# esp8266-dev-board.net
KiCad netlist of a schematic drawn in EAGLE
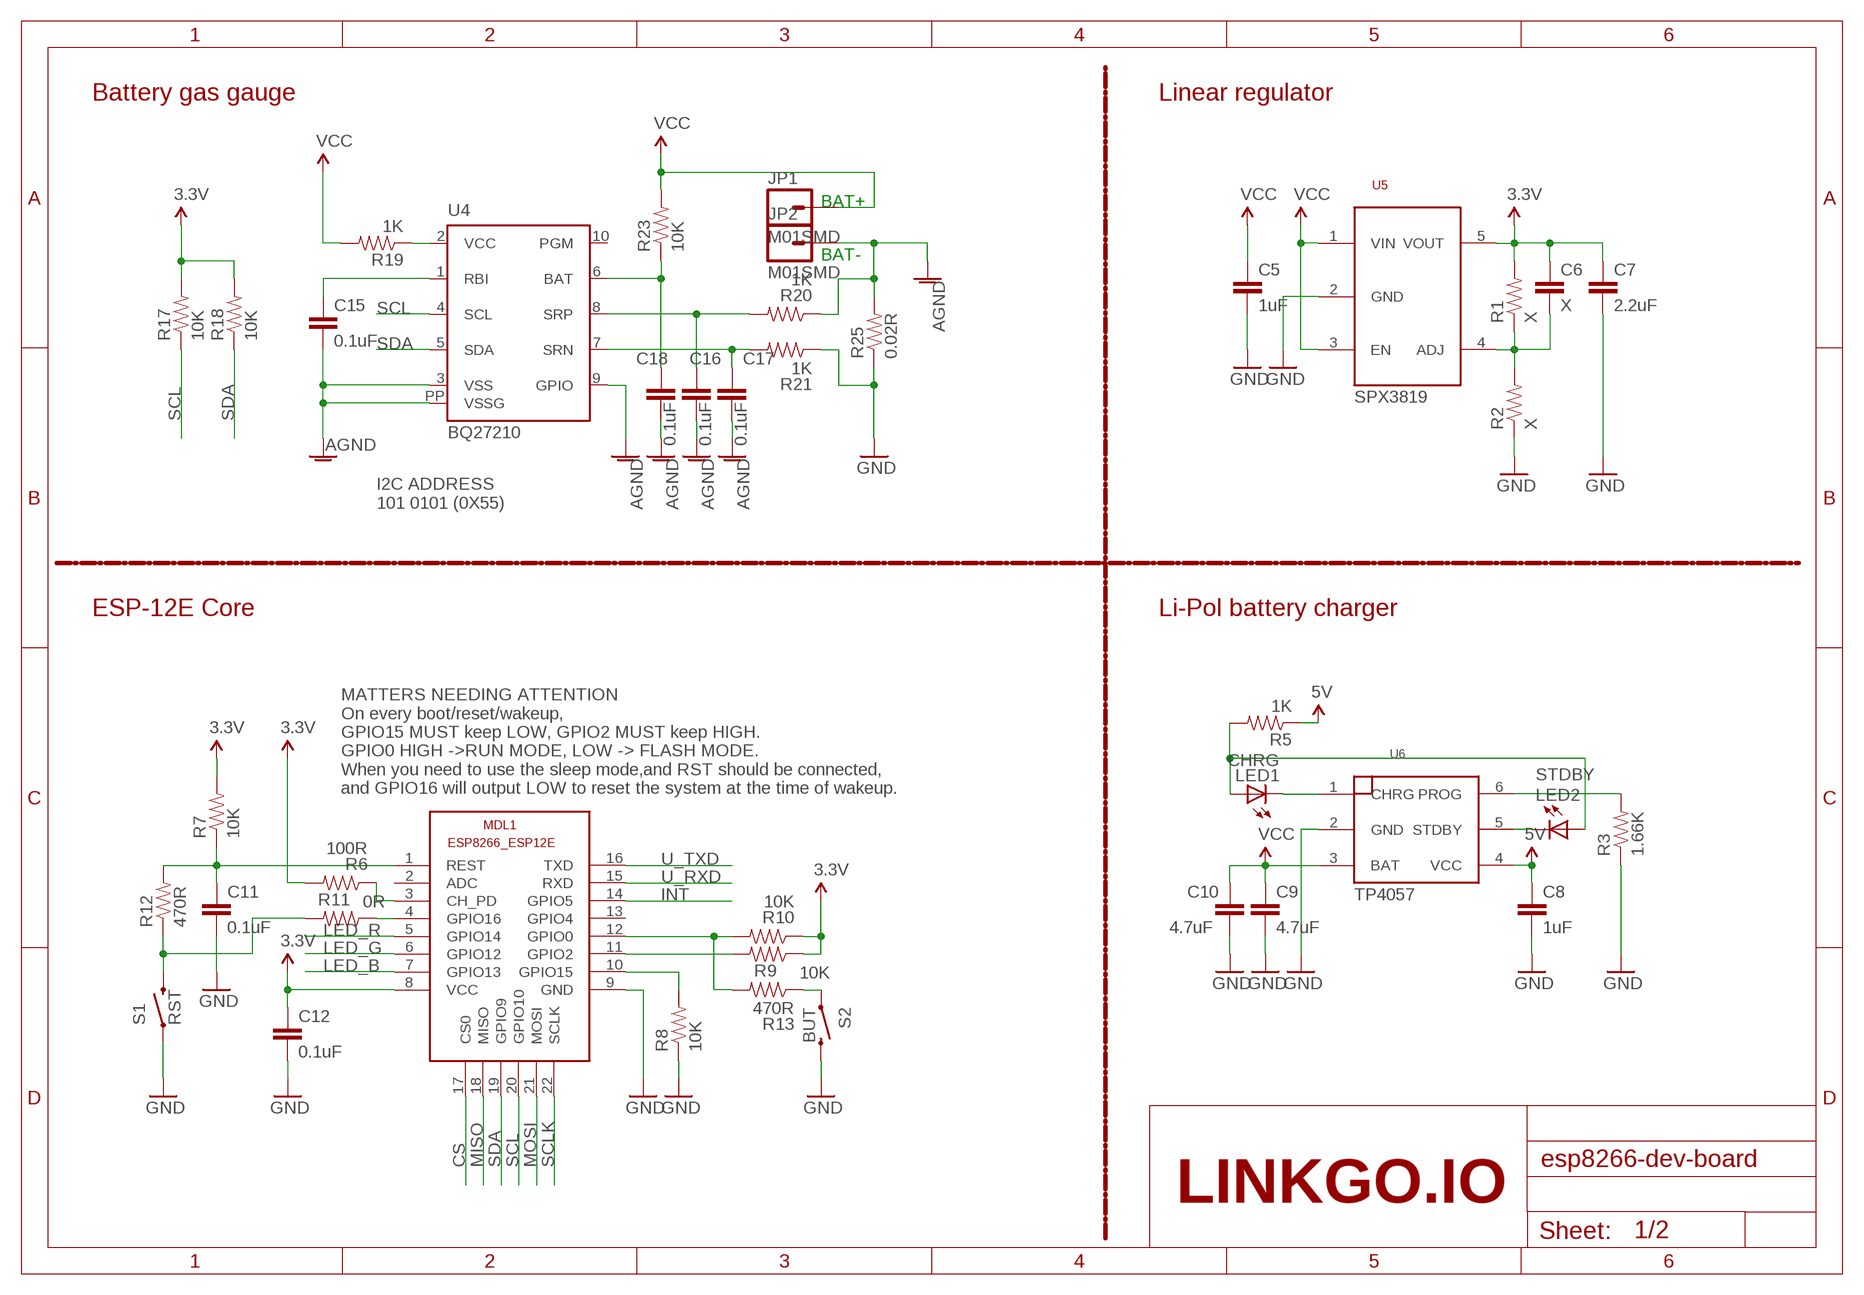
[diagram p0: schematic, sheet 1]
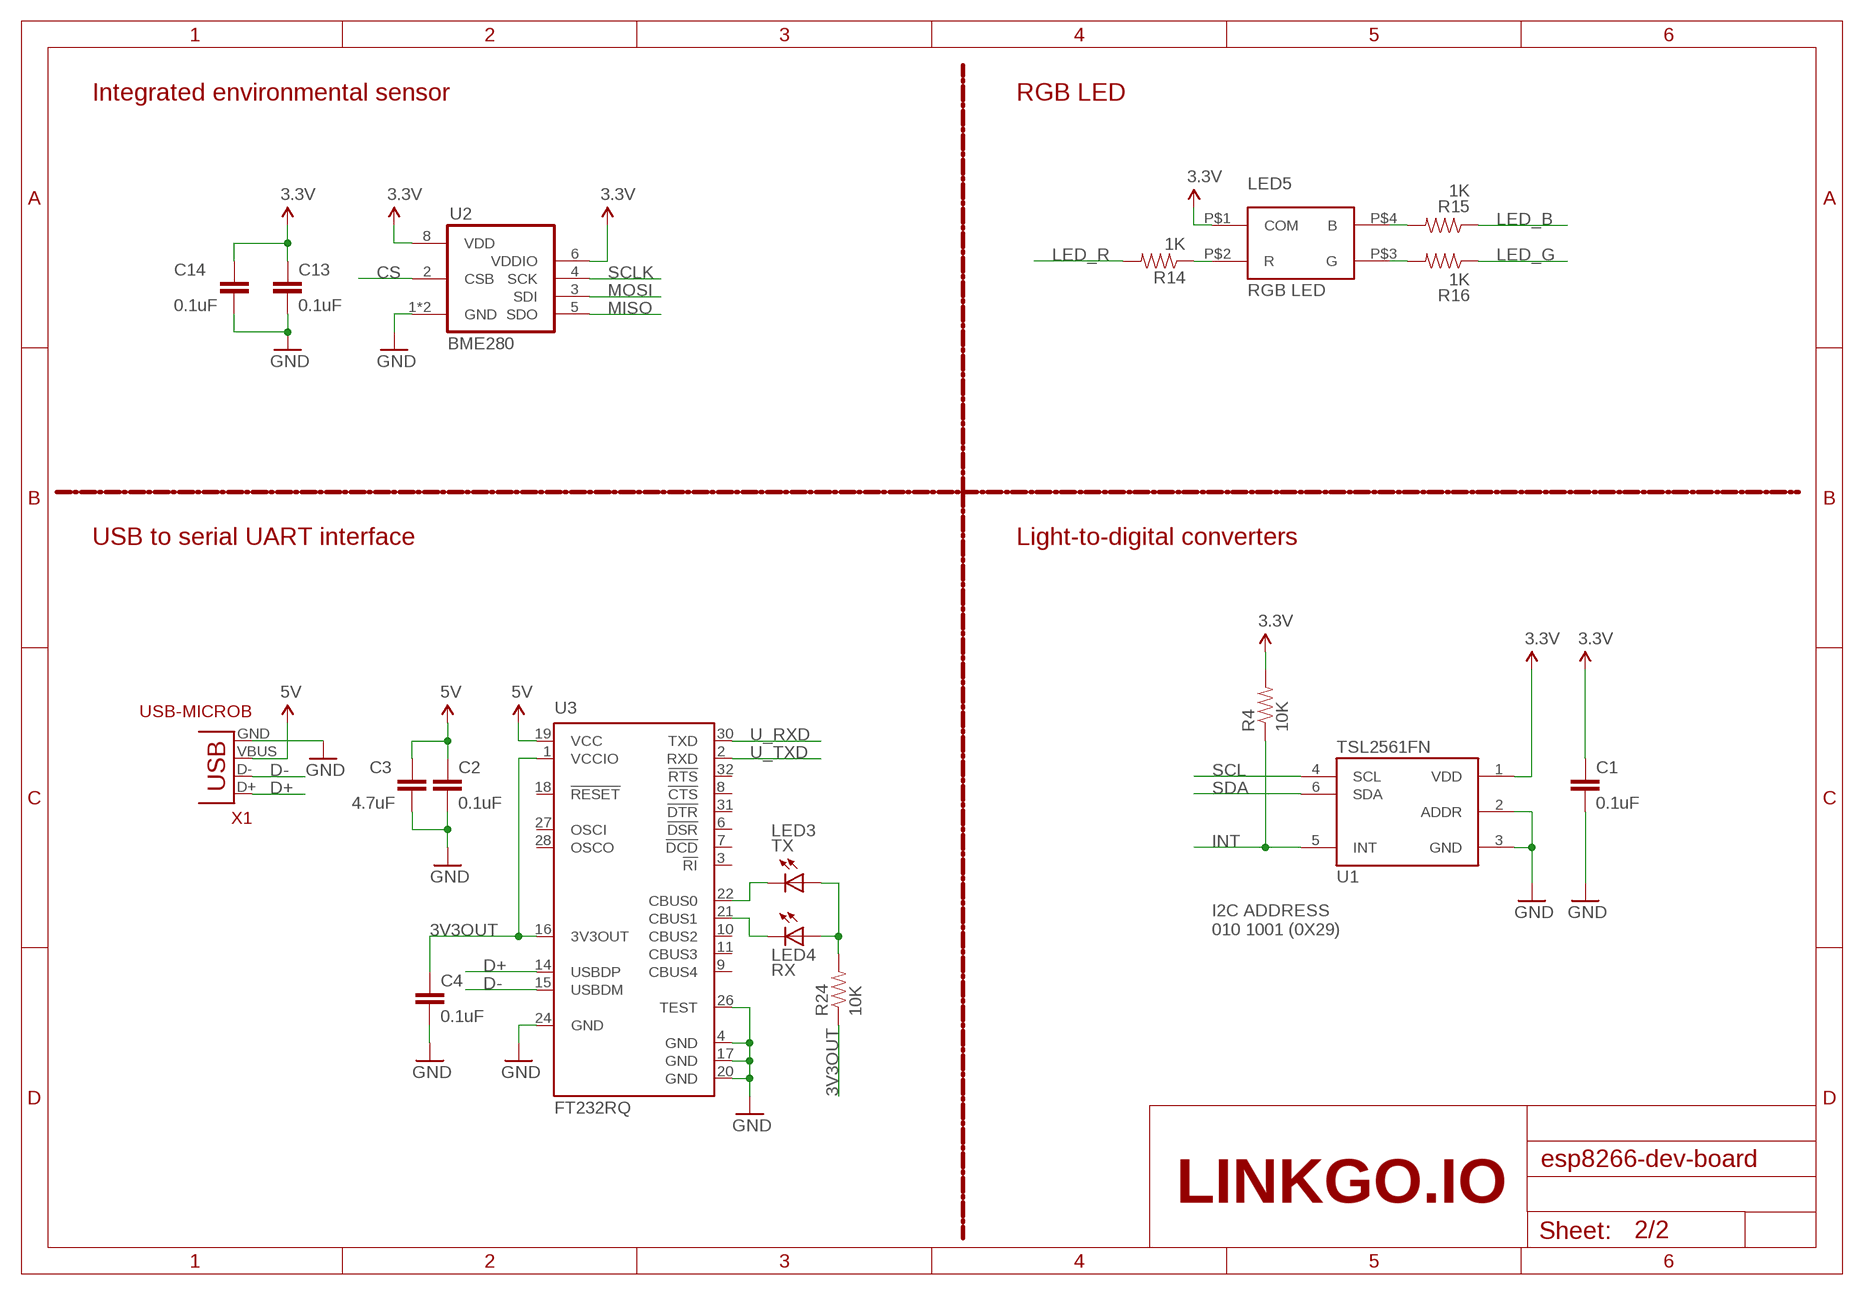
[diagram p1: schematic, sheet 2]

(export (version "E")
  (design (tool "Eeschema 10.0.6"))
  (components
    (comp (ref "C1")
      (value "0.1uF")
      (footprint "eagle-import:0603-CAP")
      (libsource (lib "eagle-import") (part "0.1UF-25V(+80/-20%)(0603)"))
    )
    (comp (ref "C2")
      (value "0.1uF")
      (footprint "eagle-import:0603-CAP")
      (libsource (lib "eagle-import") (part "0.1UF-25V(+80/-20%)(0603)"))
    )
    (comp (ref "C3")
      (value "4.7uF")
      (footprint "eagle-import:0603-CAP")
      (libsource (lib "eagle-import") (part "0.1UF-25V(+80/-20%)(0603)"))
    )
    (comp (ref "C4")
      (value "0.1uF")
      (footprint "eagle-import:0603-CAP")
      (libsource (lib "eagle-import") (part "0.1UF-25V(+80/-20%)(0603)"))
    )
    (comp (ref "C13")
      (value "0.1uF")
      (footprint "eagle-import:0603-CAP")
      (libsource (lib "eagle-import") (part "0.1UF-25V(+80/-20%)(0603)"))
    )
    (comp (ref "C14")
      (value "0.1uF")
      (footprint "eagle-import:0603-CAP")
      (libsource (lib "eagle-import") (part "0.1UF-25V(+80/-20%)(0603)"))
    )
    (comp (ref "LED3")
      (value "TX")
      (footprint "eagle-import:LED-0603")
      (libsource (lib "eagle-import") (part "LED0603"))
    )
    (comp (ref "LED4")
      (value "RX")
      (footprint "eagle-import:LED-0603")
      (libsource (lib "eagle-import") (part "LED0603"))
    )
    (comp (ref "LED5")
      (value "0603RGB")
      (footprint "eagle-import:0603RGB")
      (libsource (lib "eagle-import") (part "0603RGB"))
    )
    (comp (ref "R4")
      (value "10K")
      (footprint "eagle-import:0603-RES")
      (libsource (lib "eagle-import") (part "10KOHM-1/10W-1%(0603)0603"))
    )
    (comp (ref "R14")
      (value "1K")
      (footprint "eagle-import:0603-RES")
      (libsource (lib "eagle-import") (part "10KOHM-1/10W-1%(0603)0603"))
    )
    (comp (ref "R15")
      (value "1K")
      (footprint "eagle-import:0603-RES")
      (libsource (lib "eagle-import") (part "10KOHM-1/10W-1%(0603)0603"))
    )
    (comp (ref "R16")
      (value "1K")
      (footprint "eagle-import:0603-RES")
      (libsource (lib "eagle-import") (part "10KOHM-1/10W-1%(0603)0603"))
    )
    (comp (ref "R24")
      (value "10K")
      (footprint "eagle-import:0603-RES")
      (libsource (lib "eagle-import") (part "10KOHM-1/10W-1%(0603)0603"))
    )
    (comp (ref "U1")
      (value "TSL2561FN")
      (footprint "eagle-import:FN-6")
      (libsource (lib "eagle-import") (part "TSL2561FN"))
    )
    (comp (ref "U2")
      (value "BME280")
      (footprint "eagle-import:BME280")
      (libsource (lib "eagle-import") (part "BME280"))
    )
    (comp (ref "U3")
      (value "FT232RQ")
      (footprint "eagle-import:QFN32")
      (libsource (lib "eagle-import") (part "FT232RQ"))
    )
    (comp (ref "X1")
      (value "USB-MICROB")
      (footprint "eagle-import:USB-MICROB")
      (libsource (lib "eagle-import") (part "USB-MICROB"))
    )
    (comp (ref "C5")
      (value "1uF")
      (footprint "eagle-import:0603-CAP")
      (libsource (lib "eagle-import") (part "0.1UF-25V(+80/-20%)(0603)"))
    )
    (comp (ref "C6")
      (value "X")
      (footprint "eagle-import:0603-CAP")
      (libsource (lib "eagle-import") (part "0.1UF-25V(+80/-20%)(0603)"))
    )
    (comp (ref "C7")
      (value "2.2uF")
      (footprint "eagle-import:0603-CAP")
      (libsource (lib "eagle-import") (part "0.1UF-25V(+80/-20%)(0603)"))
    )
    (comp (ref "C8")
      (value "1uF")
      (footprint "eagle-import:0603-CAP")
      (libsource (lib "eagle-import") (part "0.1UF-25V(+80/-20%)(0603)"))
    )
    (comp (ref "C9")
      (value "4.7uF")
      (footprint "eagle-import:0603-CAP")
      (libsource (lib "eagle-import") (part "0.1UF-25V(+80/-20%)(0603)"))
    )
    (comp (ref "C10")
      (value "4.7uF")
      (footprint "eagle-import:0603-CAP")
      (libsource (lib "eagle-import") (part "0.1UF-25V(+80/-20%)(0603)"))
    )
    (comp (ref "C11")
      (value "0.1uF")
      (footprint "eagle-import:0603-CAP")
      (libsource (lib "eagle-import") (part "0.1UF-25V(+80/-20%)(0603)"))
    )
    (comp (ref "C12")
      (value "0.1uF")
      (footprint "eagle-import:0603-CAP")
      (libsource (lib "eagle-import") (part "0.1UF-25V(+80/-20%)(0603)"))
    )
    (comp (ref "C15")
      (value "0.1uF")
      (footprint "eagle-import:0603-CAP")
      (libsource (lib "eagle-import") (part "0.1UF-25V(+80/-20%)(0603)"))
    )
    (comp (ref "C16")
      (value "0.1uF")
      (footprint "eagle-import:0603-CAP")
      (libsource (lib "eagle-import") (part "0.1UF-25V(+80/-20%)(0603)"))
    )
    (comp (ref "C17")
      (value "0.1uF")
      (footprint "eagle-import:0603-CAP")
      (libsource (lib "eagle-import") (part "0.1UF-25V(+80/-20%)(0603)"))
    )
    (comp (ref "C18")
      (value "0.1uF")
      (footprint "eagle-import:0603-CAP")
      (libsource (lib "eagle-import") (part "0.1UF-25V(+80/-20%)(0603)"))
    )
    (comp (ref "JP1")
      (value "M01SMD")
      (footprint "eagle-import:LUXEON-PAD")
      (libsource (lib "eagle-import") (part "M01SMD"))
    )
    (comp (ref "JP2")
      (value "M01SMD")
      (footprint "eagle-import:LUXEON-PAD")
      (libsource (lib "eagle-import") (part "M01SMD"))
    )
    (comp (ref "LED1")
      (value "CHRG")
      (footprint "eagle-import:LED-0603")
      (libsource (lib "eagle-import") (part "LED0603"))
    )
    (comp (ref "LED2")
      (value "STDBY")
      (footprint "eagle-import:LED-0603")
      (libsource (lib "eagle-import") (part "LED0603"))
    )
    (comp (ref "MDL1")
      (value "ESP8266-12EESP8266-ESP12E")
      (footprint "eagle-import:ESP8266-ESP12E")
      (libsource (lib "eagle-import") (part "ESP8266-12EESP8266-ESP12E"))
    )
    (comp (ref "R1")
      (value "X")
      (footprint "eagle-import:0603-RES")
      (libsource (lib "eagle-import") (part "10KOHM-1/10W-1%(0603)0603"))
    )
    (comp (ref "R2")
      (value "X")
      (footprint "eagle-import:0603-RES")
      (libsource (lib "eagle-import") (part "10KOHM-1/10W-1%(0603)0603"))
    )
    (comp (ref "R3")
      (value "1.66K")
      (footprint "eagle-import:0603-RES")
      (libsource (lib "eagle-import") (part "10KOHM-1/10W-1%(0603)0603"))
    )
    (comp (ref "R5")
      (value "1K")
      (footprint "eagle-import:0603-RES")
      (libsource (lib "eagle-import") (part "10KOHM-1/10W-1%(0603)0603"))
    )
    (comp (ref "R6")
      (value "100R")
      (footprint "eagle-import:0603-RES")
      (libsource (lib "eagle-import") (part "10KOHM-1/10W-1%(0603)0603"))
    )
    (comp (ref "R7")
      (value "10K")
      (footprint "eagle-import:0603-RES")
      (libsource (lib "eagle-import") (part "10KOHM-1/10W-1%(0603)0603"))
    )
    (comp (ref "R8")
      (value "10K")
      (footprint "eagle-import:0603-RES")
      (libsource (lib "eagle-import") (part "10KOHM-1/10W-1%(0603)0603"))
    )
    (comp (ref "R9")
      (value "10K")
      (footprint "eagle-import:0603-RES")
      (libsource (lib "eagle-import") (part "10KOHM-1/10W-1%(0603)0603"))
    )
    (comp (ref "R10")
      (value "10K")
      (footprint "eagle-import:0603-RES")
      (libsource (lib "eagle-import") (part "10KOHM-1/10W-1%(0603)0603"))
    )
    (comp (ref "R11")
      (value "0R")
      (footprint "eagle-import:0603-RES")
      (libsource (lib "eagle-import") (part "10KOHM-1/10W-1%(0603)0603"))
    )
    (comp (ref "R12")
      (value "470R")
      (footprint "eagle-import:0603-RES")
      (libsource (lib "eagle-import") (part "10KOHM-1/10W-1%(0603)0603"))
    )
    (comp (ref "R13")
      (value "470R")
      (footprint "eagle-import:0603-RES")
      (libsource (lib "eagle-import") (part "10KOHM-1/10W-1%(0603)0603"))
    )
    (comp (ref "R17")
      (value "10K")
      (footprint "eagle-import:0603-RES")
      (libsource (lib "eagle-import") (part "10KOHM-1/10W-1%(0603)0603"))
    )
    (comp (ref "R18")
      (value "10K")
      (footprint "eagle-import:0603-RES")
      (libsource (lib "eagle-import") (part "10KOHM-1/10W-1%(0603)0603"))
    )
    (comp (ref "R19")
      (value "1K")
      (footprint "eagle-import:0603-RES")
      (libsource (lib "eagle-import") (part "10KOHM-1/10W-1%(0603)0603"))
    )
    (comp (ref "R20")
      (value "1K")
      (footprint "eagle-import:0603-RES")
      (libsource (lib "eagle-import") (part "10KOHM-1/10W-1%(0603)0603"))
    )
    (comp (ref "R21")
      (value "1K")
      (footprint "eagle-import:0603-RES")
      (libsource (lib "eagle-import") (part "10KOHM-1/10W-1%(0603)0603"))
    )
    (comp (ref "R23")
      (value "10K")
      (footprint "eagle-import:0603-RES")
      (libsource (lib "eagle-import") (part "10KOHM-1/10W-1%(0603)0603"))
    )
    (comp (ref "R25")
      (value "0.02R")
      (footprint "eagle-import:1206")
      (libsource (lib "eagle-import") (part "RESISTOR1206"))
    )
    (comp (ref "S1")
      (value "RST")
      (footprint "eagle-import:TACTILE-SWITCH-1101NE")
      (libsource (lib "eagle-import") (part "SWITCH-MOMENTARY-2-SMD-1101NE"))
    )
    (comp (ref "S2")
      (value "BUT")
      (footprint "eagle-import:TACTILE-SWITCH-1101NE")
      (libsource (lib "eagle-import") (part "SWITCH-MOMENTARY-2-SMD-1101NE"))
    )
    (comp (ref "U4")
      (value "BQ27210")
      (footprint "eagle-import:DRK_S-PDSO-N10")
      (fields (field (name "MPN") "BQ27210DRKR"))
      (libsource (lib "eagle-import") (part "BQ27210"))
    )
    (comp (ref "U5")
      (value "SPX3819M5-ADJ")
      (footprint "eagle-import:SOT23-5")
      (libsource (lib "eagle-import") (part "SPX3819M5-ADJ"))
    )
    (comp (ref "U6")
      (value "TP4057")
      (footprint "eagle-import:SOT23-6")
      (libsource (lib "eagle-import") (part "TP4057"))
    )
  )
  (nets
    (net (code "1") (name "3.3V") (class "Default")
      (node (ref "C1") (pin "1") (pinfunction "1_1") (pintype "passive"))
      (node (ref "C12") (pin "1") (pinfunction "1_1") (pintype "passive"))
      (node (ref "C13") (pin "1") (pinfunction "1_1") (pintype "passive"))
      (node (ref "C14") (pin "1") (pinfunction "1_1") (pintype "passive"))
      (node (ref "C6") (pin "1") (pinfunction "1_1") (pintype "passive"))
      (node (ref "C7") (pin "1") (pinfunction "1_1") (pintype "passive"))
      (node (ref "LED5") (pin "P$1") (pinfunction "COM_P$1") (pintype "bidirectional"))
      (node (ref "MDL1") (pin "8") (pinfunction "VCC_8") (pintype "bidirectional"))
      (node (ref "R1") (pin "2") (pinfunction "2_2") (pintype "passive"))
      (node (ref "R10") (pin "1") (pinfunction "1_1") (pintype "passive"))
      (node (ref "R17") (pin "2") (pinfunction "2_2") (pintype "passive"))
      (node (ref "R18") (pin "2") (pinfunction "2_2") (pintype "passive"))
      (node (ref "R4") (pin "2") (pinfunction "2_2") (pintype "passive"))
      (node (ref "R6") (pin "2") (pinfunction "2_2") (pintype "passive"))
      (node (ref "R7") (pin "2") (pinfunction "2_2") (pintype "passive"))
      (node (ref "R9") (pin "1") (pinfunction "1_1") (pintype "passive"))
      (node (ref "U1") (pin "1") (pinfunction "VDD_1") (pintype "power_in"))
      (node (ref "U2") (pin "6") (pinfunction "VDDIO_6") (pintype "power_in"))
      (node (ref "U2") (pin "8") (pinfunction "VDD_8") (pintype "power_in"))
      (node (ref "U5") (pin "5") (pinfunction "VOUT_5") (pintype "bidirectional"))
    )
    (net (code "2") (name "3V3OUT") (class "Default")
      (node (ref "C4") (pin "1") (pinfunction "1_1") (pintype "passive"))
      (node (ref "R24") (pin "1") (pinfunction "1_1") (pintype "passive"))
      (node (ref "U3") (pin "1") (pinfunction "VCCIO_1") (pintype "power_in"))
      (node (ref "U3") (pin "16") (pinfunction "3V3OUT_16") (pintype "output"))
    )
    (net (code "3") (name "5V") (class "Default")
      (node (ref "C2") (pin "1") (pinfunction "1_1") (pintype "passive"))
      (node (ref "C3") (pin "1") (pinfunction "1_1") (pintype "passive"))
      (node (ref "C8") (pin "1") (pinfunction "1_1") (pintype "passive"))
      (node (ref "R5") (pin "1") (pinfunction "1_1") (pintype "passive"))
      (node (ref "U3") (pin "19") (pinfunction "VCC_19") (pintype "power_in"))
      (node (ref "U6") (pin "4") (pinfunction "VCC_4") (pintype "bidirectional"))
      (node (ref "X1") (pin "VBUS") (pinfunction "VBUS_VBUS") (pintype "bidirectional"))
    )
    (net (code "4") (name "AGND") (class "Default")
      (node (ref "C15") (pin "2") (pinfunction "2_2") (pintype "passive"))
      (node (ref "C16") (pin "2") (pinfunction "2_2") (pintype "passive"))
      (node (ref "C17") (pin "2") (pinfunction "2_2") (pintype "passive"))
      (node (ref "C18") (pin "2") (pinfunction "2_2") (pintype "passive"))
      (node (ref "JP2") (pin "P$1") (pinfunction "1_P$1") (pintype "passive"))
      (node (ref "R20") (pin "1") (pinfunction "1_1") (pintype "passive"))
      (node (ref "R25") (pin "2") (pinfunction "2_2") (pintype "passive"))
      (node (ref "U4") (pin "3") (pinfunction "VSS_3") (pintype "input"))
      (node (ref "U4") (pin "9") (pinfunction "GPIO_9") (pintype "bidirectional"))
      (node (ref "U4") (pin "PP") (pinfunction "VSSG_PP") (pintype "input"))
    )
    (net (code "5") (name "CS") (class "Default")
      (node (ref "MDL1") (pin "17") (pinfunction "CS0_17") (pintype "bidirectional"))
      (node (ref "U2") (pin "2") (pinfunction "CSB_2") (pintype "input"))
    )
    (net (code "6") (name "D+") (class "Default")
      (node (ref "U3") (pin "14") (pinfunction "USBDP_14") (pintype "bidirectional"))
      (node (ref "X1") (pin "D+") (pinfunction "D+_D+") (pintype "bidirectional"))
    )
    (net (code "7") (name "D-") (class "Default")
      (node (ref "U3") (pin "15") (pinfunction "USBDM_15") (pintype "bidirectional"))
      (node (ref "X1") (pin "D-") (pinfunction "D-_D-") (pintype "bidirectional"))
    )
    (net (code "8") (name "GND") (class "Default")
      (node (ref "C1") (pin "2") (pinfunction "2_2") (pintype "passive"))
      (node (ref "C10") (pin "2") (pinfunction "2_2") (pintype "passive"))
      (node (ref "C11") (pin "2") (pinfunction "2_2") (pintype "passive"))
      (node (ref "C12") (pin "2") (pinfunction "2_2") (pintype "passive"))
      (node (ref "C13") (pin "2") (pinfunction "2_2") (pintype "passive"))
      (node (ref "C14") (pin "2") (pinfunction "2_2") (pintype "passive"))
      (node (ref "C2") (pin "2") (pinfunction "2_2") (pintype "passive"))
      (node (ref "C3") (pin "2") (pinfunction "2_2") (pintype "passive"))
      (node (ref "C4") (pin "2") (pinfunction "2_2") (pintype "passive"))
      (node (ref "C5") (pin "2") (pinfunction "2_2") (pintype "passive"))
      (node (ref "C7") (pin "2") (pinfunction "2_2") (pintype "passive"))
      (node (ref "C8") (pin "2") (pinfunction "2_2") (pintype "passive"))
      (node (ref "C9") (pin "2") (pinfunction "2_2") (pintype "passive"))
      (node (ref "MDL1") (pin "9") (pinfunction "GND_9") (pintype "bidirectional"))
      (node (ref "R2") (pin "1") (pinfunction "1_1") (pintype "passive"))
      (node (ref "R21") (pin "1") (pinfunction "1_1") (pintype "passive"))
      (node (ref "R25") (pin "1") (pinfunction "1_1") (pintype "passive"))
      (node (ref "R3") (pin "1") (pinfunction "1_1") (pintype "passive"))
      (node (ref "R8") (pin "1") (pinfunction "1_1") (pintype "passive"))
      (node (ref "S1") (pin "P$1") (pinfunction "1_P$1") (pintype "passive"))
      (node (ref "S2") (pin "P$2") (pinfunction "2_P$2") (pintype "passive"))
      (node (ref "U1") (pin "2") (pinfunction "ADDR_2") (pintype "input"))
      (node (ref "U1") (pin "3") (pinfunction "GND_3") (pintype "power_in"))
      (node (ref "U2") (pin "1") (pinfunction "GND_1") (pintype "power_in"))
      (node (ref "U2") (pin "7") (pinfunction "GND_7") (pintype "power_in"))
      (node (ref "U3") (pin "17") (pinfunction "GND_17") (pintype "power_in"))
      (node (ref "U3") (pin "20") (pinfunction "GND_20") (pintype "power_in"))
      (node (ref "U3") (pin "24") (pinfunction "GND_24") (pintype "power_in"))
      (node (ref "U3") (pin "26") (pinfunction "TEST_26") (pintype "input"))
      (node (ref "U3") (pin "4") (pinfunction "GND_4") (pintype "power_in"))
      (node (ref "U5") (pin "2") (pinfunction "GND_2") (pintype "bidirectional"))
      (node (ref "U6") (pin "2") (pinfunction "GND_2") (pintype "bidirectional"))
      (node (ref "X1") (pin "GND") (pinfunction "GND_GND") (pintype "bidirectional"))
    )
    (net (code "9") (name "INT") (class "Default")
      (node (ref "MDL1") (pin "14") (pinfunction "GPIO5_14") (pintype "bidirectional"))
      (node (ref "R4") (pin "1") (pinfunction "1_1") (pintype "passive"))
      (node (ref "U1") (pin "5") (pinfunction "INT_5") (pintype "output"))
    )
    (net (code "10") (name "LED_B") (class "Default")
      (node (ref "MDL1") (pin "7") (pinfunction "GPIO13_7") (pintype "bidirectional"))
      (node (ref "R15") (pin "1") (pinfunction "1_1") (pintype "passive"))
    )
    (net (code "11") (name "LED_G") (class "Default")
      (node (ref "MDL1") (pin "6") (pinfunction "GPIO12_6") (pintype "bidirectional"))
      (node (ref "R16") (pin "1") (pinfunction "1_1") (pintype "passive"))
    )
    (net (code "12") (name "LED_R") (class "Default")
      (node (ref "MDL1") (pin "5") (pinfunction "GPIO14_5") (pintype "bidirectional"))
      (node (ref "R14") (pin "2") (pinfunction "2_2") (pintype "passive"))
    )
    (net (code "13") (name "MISO") (class "Default")
      (node (ref "MDL1") (pin "18") (pinfunction "MISO_18") (pintype "bidirectional"))
      (node (ref "U2") (pin "5") (pinfunction "SDO_5") (pintype "input"))
    )
    (net (code "14") (name "MOSI") (class "Default")
      (node (ref "MDL1") (pin "21") (pinfunction "MOSI_21") (pintype "bidirectional"))
      (node (ref "U2") (pin "3") (pinfunction "SDI_3") (pintype "bidirectional"))
    )
    (net (code "15") (name "Net-(LED1-PadA)") (class "Default")
      (node (ref "LED1") (pin "A") (pinfunction "A_A") (pintype "passive"))
      (node (ref "LED2") (pin "A") (pinfunction "A_A") (pintype "passive"))
      (node (ref "R5") (pin "2") (pinfunction "2_2") (pintype "passive"))
    )
    (net (code "16") (name "Net-(LED3-PadA)") (class "Default")
      (node (ref "LED3") (pin "A") (pinfunction "A_A") (pintype "passive"))
      (node (ref "LED4") (pin "A") (pinfunction "A_A") (pintype "passive"))
      (node (ref "R24") (pin "2") (pinfunction "2_2") (pintype "passive"))
    )
    (net (code "17") (name "Net-(LED5-B)") (class "Default")
      (node (ref "LED5") (pin "P$4") (pinfunction "B_P$4") (pintype "bidirectional"))
      (node (ref "R15") (pin "2") (pinfunction "2_2") (pintype "passive"))
    )
    (net (code "18") (name "Net-(LED5-G)") (class "Default")
      (node (ref "LED5") (pin "P$3") (pinfunction "G_P$3") (pintype "bidirectional"))
      (node (ref "R16") (pin "2") (pinfunction "2_2") (pintype "passive"))
    )
    (net (code "19") (name "Net-(LED5-R)") (class "Default")
      (node (ref "LED5") (pin "P$2") (pinfunction "R_P$2") (pintype "bidirectional"))
      (node (ref "R14") (pin "1") (pinfunction "1_1") (pintype "passive"))
    )
    (net (code "20") (name "Net-(MDL1-CH_PD)") (class "Default")
      (node (ref "MDL1") (pin "3") (pinfunction "CH_PD_3") (pintype "bidirectional"))
      (node (ref "R6") (pin "1") (pinfunction "1_1") (pintype "passive"))
    )
    (net (code "21") (name "Net-(MDL1-GPIO0)") (class "Default")
      (node (ref "MDL1") (pin "12") (pinfunction "GPIO0_12") (pintype "bidirectional"))
      (node (ref "R10") (pin "2") (pinfunction "2_2") (pintype "passive"))
      (node (ref "R13") (pin "2") (pinfunction "2_2") (pintype "passive"))
    )
    (net (code "22") (name "Net-(MDL1-GPIO2)") (class "Default")
      (node (ref "MDL1") (pin "11") (pinfunction "GPIO2_11") (pintype "bidirectional"))
      (node (ref "R9") (pin "2") (pinfunction "2_2") (pintype "passive"))
    )
    (net (code "23") (name "Net-(MDL1-GPIO15)") (class "Default")
      (node (ref "MDL1") (pin "10") (pinfunction "GPIO15_10") (pintype "bidirectional"))
      (node (ref "R8") (pin "2") (pinfunction "2_2") (pintype "passive"))
    )
    (net (code "24") (name "Net-(MDL1-GPIO16)") (class "Default")
      (node (ref "MDL1") (pin "4") (pinfunction "GPIO16_4") (pintype "bidirectional"))
      (node (ref "R11") (pin "1") (pinfunction "1_1") (pintype "passive"))
    )
    (net (code "25") (name "Net-(MDL1-REST)") (class "Default")
      (node (ref "C11") (pin "1") (pinfunction "1_1") (pintype "passive"))
      (node (ref "MDL1") (pin "1") (pinfunction "REST_1") (pintype "bidirectional"))
      (node (ref "R12") (pin "2") (pinfunction "2_2") (pintype "passive"))
      (node (ref "R7") (pin "1") (pinfunction "1_1") (pintype "passive"))
    )
    (net (code "26") (name "Net-(S1-2)") (class "Default")
      (node (ref "R11") (pin "2") (pinfunction "2_2") (pintype "passive"))
      (node (ref "R12") (pin "1") (pinfunction "1_1") (pintype "passive"))
      (node (ref "S1") (pin "P$2") (pinfunction "2_P$2") (pintype "passive"))
    )
    (net (code "27") (name "Net-(S2-1)") (class "Default")
      (node (ref "R13") (pin "1") (pinfunction "1_1") (pintype "passive"))
      (node (ref "S2") (pin "P$1") (pinfunction "1_P$1") (pintype "passive"))
    )
    (net (code "28") (name "Net-(U3-CBUS0)") (class "Default")
      (node (ref "LED3") (pin "C") (pinfunction "C_C") (pintype "passive"))
      (node (ref "U3") (pin "22") (pinfunction "CBUS0_22") (pintype "bidirectional"))
    )
    (net (code "29") (name "Net-(U3-CBUS1)") (class "Default")
      (node (ref "LED4") (pin "C") (pinfunction "C_C") (pintype "passive"))
      (node (ref "U3") (pin "21") (pinfunction "CBUS1_21") (pintype "bidirectional"))
    )
    (net (code "30") (name "Net-(U4A-BAT)") (class "Default")
      (node (ref "C18") (pin "1") (pinfunction "1_1") (pintype "passive"))
      (node (ref "R23") (pin "1") (pinfunction "1_1") (pintype "passive"))
      (node (ref "U4") (pin "6") (pinfunction "BAT_6") (pintype "input"))
    )
    (net (code "31") (name "Net-(U4A-RBI)") (class "Default")
      (node (ref "C15") (pin "1") (pinfunction "1_1") (pintype "passive"))
      (node (ref "U4") (pin "1") (pinfunction "RBI_1") (pintype "input"))
    )
    (net (code "32") (name "Net-(U4A-SRN)") (class "Default")
      (node (ref "C17") (pin "1") (pinfunction "1_1") (pintype "passive"))
      (node (ref "R21") (pin "2") (pinfunction "2_2") (pintype "passive"))
      (node (ref "U4") (pin "7") (pinfunction "SRN_7") (pintype "input"))
    )
    (net (code "33") (name "Net-(U4A-SRP)") (class "Default")
      (node (ref "C16") (pin "1") (pinfunction "1_1") (pintype "passive"))
      (node (ref "R20") (pin "2") (pinfunction "2_2") (pintype "passive"))
      (node (ref "U4") (pin "8") (pinfunction "SRP_8") (pintype "input"))
    )
    (net (code "34") (name "Net-(U4A-VCC)") (class "Default")
      (node (ref "R19") (pin "1") (pinfunction "1_1") (pintype "passive"))
      (node (ref "U4") (pin "2") (pinfunction "VCC_2") (pintype "input"))
    )
    (net (code "35") (name "Net-(U5-ADJ)") (class "Default")
      (node (ref "C6") (pin "2") (pinfunction "2_2") (pintype "passive"))
      (node (ref "R1") (pin "1") (pinfunction "1_1") (pintype "passive"))
      (node (ref "R2") (pin "2") (pinfunction "2_2") (pintype "passive"))
      (node (ref "U5") (pin "4") (pinfunction "ADJ_4") (pintype "bidirectional"))
    )
    (net (code "36") (name "Net-(U6-CHRG)") (class "Default")
      (node (ref "LED1") (pin "C") (pinfunction "C_C") (pintype "passive"))
      (node (ref "U6") (pin "1") (pinfunction "CHRG_1") (pintype "bidirectional"))
    )
    (net (code "37") (name "Net-(U6-PROG)") (class "Default")
      (node (ref "R3") (pin "2") (pinfunction "2_2") (pintype "passive"))
      (node (ref "U6") (pin "6") (pinfunction "PROG_6") (pintype "bidirectional"))
    )
    (net (code "38") (name "Net-(U6-STDBY)") (class "Default")
      (node (ref "LED2") (pin "C") (pinfunction "C_C") (pintype "passive"))
      (node (ref "U6") (pin "5") (pinfunction "STDBY_5") (pintype "bidirectional"))
    )
    (net (code "39") (name "SCL") (class "Default")
      (node (ref "MDL1") (pin "20") (pinfunction "GPIO10_20") (pintype "bidirectional"))
      (node (ref "R17") (pin "1") (pinfunction "1_1") (pintype "passive"))
      (node (ref "U1") (pin "4") (pinfunction "SCL_4") (pintype "input"))
      (node (ref "U4") (pin "4") (pinfunction "SCL_4") (pintype "input"))
    )
    (net (code "40") (name "SCLK") (class "Default")
      (node (ref "MDL1") (pin "22") (pinfunction "SCLK_22") (pintype "bidirectional"))
      (node (ref "U2") (pin "4") (pinfunction "SCK_4") (pintype "bidirectional"))
    )
    (net (code "41") (name "SDA") (class "Default")
      (node (ref "MDL1") (pin "19") (pinfunction "GPIO9_19") (pintype "bidirectional"))
      (node (ref "R18") (pin "1") (pinfunction "1_1") (pintype "passive"))
      (node (ref "U1") (pin "6") (pinfunction "SDA_6") (pintype "bidirectional"))
      (node (ref "U4") (pin "5") (pinfunction "SDA_5") (pintype "bidirectional"))
    )
    (net (code "42") (name "U_RXD") (class "Default")
      (node (ref "MDL1") (pin "15") (pinfunction "RXD_15") (pintype "bidirectional"))
      (node (ref "U3") (pin "30") (pinfunction "TXD_30") (pintype "output"))
    )
    (net (code "43") (name "U_TXD") (class "Default")
      (node (ref "MDL1") (pin "16") (pinfunction "TXD_16") (pintype "bidirectional"))
      (node (ref "U3") (pin "2") (pinfunction "RXD_2") (pintype "input"))
    )
    (net (code "44") (name "VCC") (class "Default")
      (node (ref "C10") (pin "1") (pinfunction "1_1") (pintype "passive"))
      (node (ref "C5") (pin "1") (pinfunction "1_1") (pintype "passive"))
      (node (ref "C9") (pin "1") (pinfunction "1_1") (pintype "passive"))
      (node (ref "JP1") (pin "P$1") (pinfunction "1_P$1") (pintype "passive"))
      (node (ref "R19") (pin "2") (pinfunction "2_2") (pintype "passive"))
      (node (ref "R23") (pin "2") (pinfunction "2_2") (pintype "passive"))
      (node (ref "U5") (pin "1") (pinfunction "VIN_1") (pintype "bidirectional"))
      (node (ref "U5") (pin "3") (pinfunction "EN_3") (pintype "bidirectional"))
      (node (ref "U6") (pin "3") (pinfunction "BAT_3") (pintype "bidirectional"))
    )
    (net (code "45") (name "unconnected-(MDL1-ADC-Pad2)") (class "Default")
      (node (ref "MDL1") (pin "2") (pinfunction "ADC_2") (pintype "bidirectional"))
    )
    (net (code "46") (name "unconnected-(MDL1-GPIO4-Pad13)") (class "Default")
      (node (ref "MDL1") (pin "13") (pinfunction "GPIO4_13") (pintype "bidirectional"))
    )
    (net (code "47") (name "unconnected-(U3-CBUS2-Pad10)") (class "Default")
      (node (ref "U3") (pin "10") (pinfunction "CBUS2_10") (pintype "bidirectional"))
    )
    (net (code "48") (name "unconnected-(U3-CBUS3-Pad11)") (class "Default")
      (node (ref "U3") (pin "11") (pinfunction "CBUS3_11") (pintype "bidirectional"))
    )
    (net (code "49") (name "unconnected-(U3-CBUS4-Pad9)") (class "Default")
      (node (ref "U3") (pin "9") (pinfunction "CBUS4_9") (pintype "bidirectional"))
    )
    (net (code "50") (name "unconnected-(U3-OSCI-Pad27)") (class "Default")
      (node (ref "U3") (pin "27") (pinfunction "OSCI_27") (pintype "input"))
    )
    (net (code "51") (name "unconnected-(U3-OSCO-Pad28)") (class "Default")
      (node (ref "U3") (pin "28") (pinfunction "OSCO_28") (pintype "output"))
    )
    (net (code "52") (name "unconnected-(U3-~{CTS}-Pad8)") (class "Default")
      (node (ref "U3") (pin "8") (pinfunction "~{CTS}_8") (pintype "input"))
    )
    (net (code "53") (name "unconnected-(U3-~{DCD}-Pad7)") (class "Default")
      (node (ref "U3") (pin "7") (pinfunction "~{DCD}_7") (pintype "input"))
    )
    (net (code "54") (name "unconnected-(U3-~{DSR}-Pad6)") (class "Default")
      (node (ref "U3") (pin "6") (pinfunction "~{DSR}_6") (pintype "input"))
    )
    (net (code "55") (name "unconnected-(U3-~{DTR}-Pad31)") (class "Default")
      (node (ref "U3") (pin "31") (pinfunction "~{DTR}_31") (pintype "output"))
    )
    (net (code "56") (name "unconnected-(U3-~{RESET}-Pad18)") (class "Default")
      (node (ref "U3") (pin "18") (pinfunction "~{RESET}_18") (pintype "input"))
    )
    (net (code "57") (name "unconnected-(U3-~{RI}-Pad3)") (class "Default")
      (node (ref "U3") (pin "3") (pinfunction "~{RI}_3") (pintype "input"))
    )
    (net (code "58") (name "unconnected-(U3-~{RTS}-Pad32)") (class "Default")
      (node (ref "U3") (pin "32") (pinfunction "~{RTS}_32") (pintype "output"))
    )
    (net (code "59") (name "unconnected-(U4A-PGM-Pad10)") (class "Default")
      (node (ref "U4") (pin "10") (pinfunction "PGM_10") (pintype "input"))
    )
  )
)
